# SCHEMATIC.net
KiCad netlist of a schematic drawn in EasyEDA
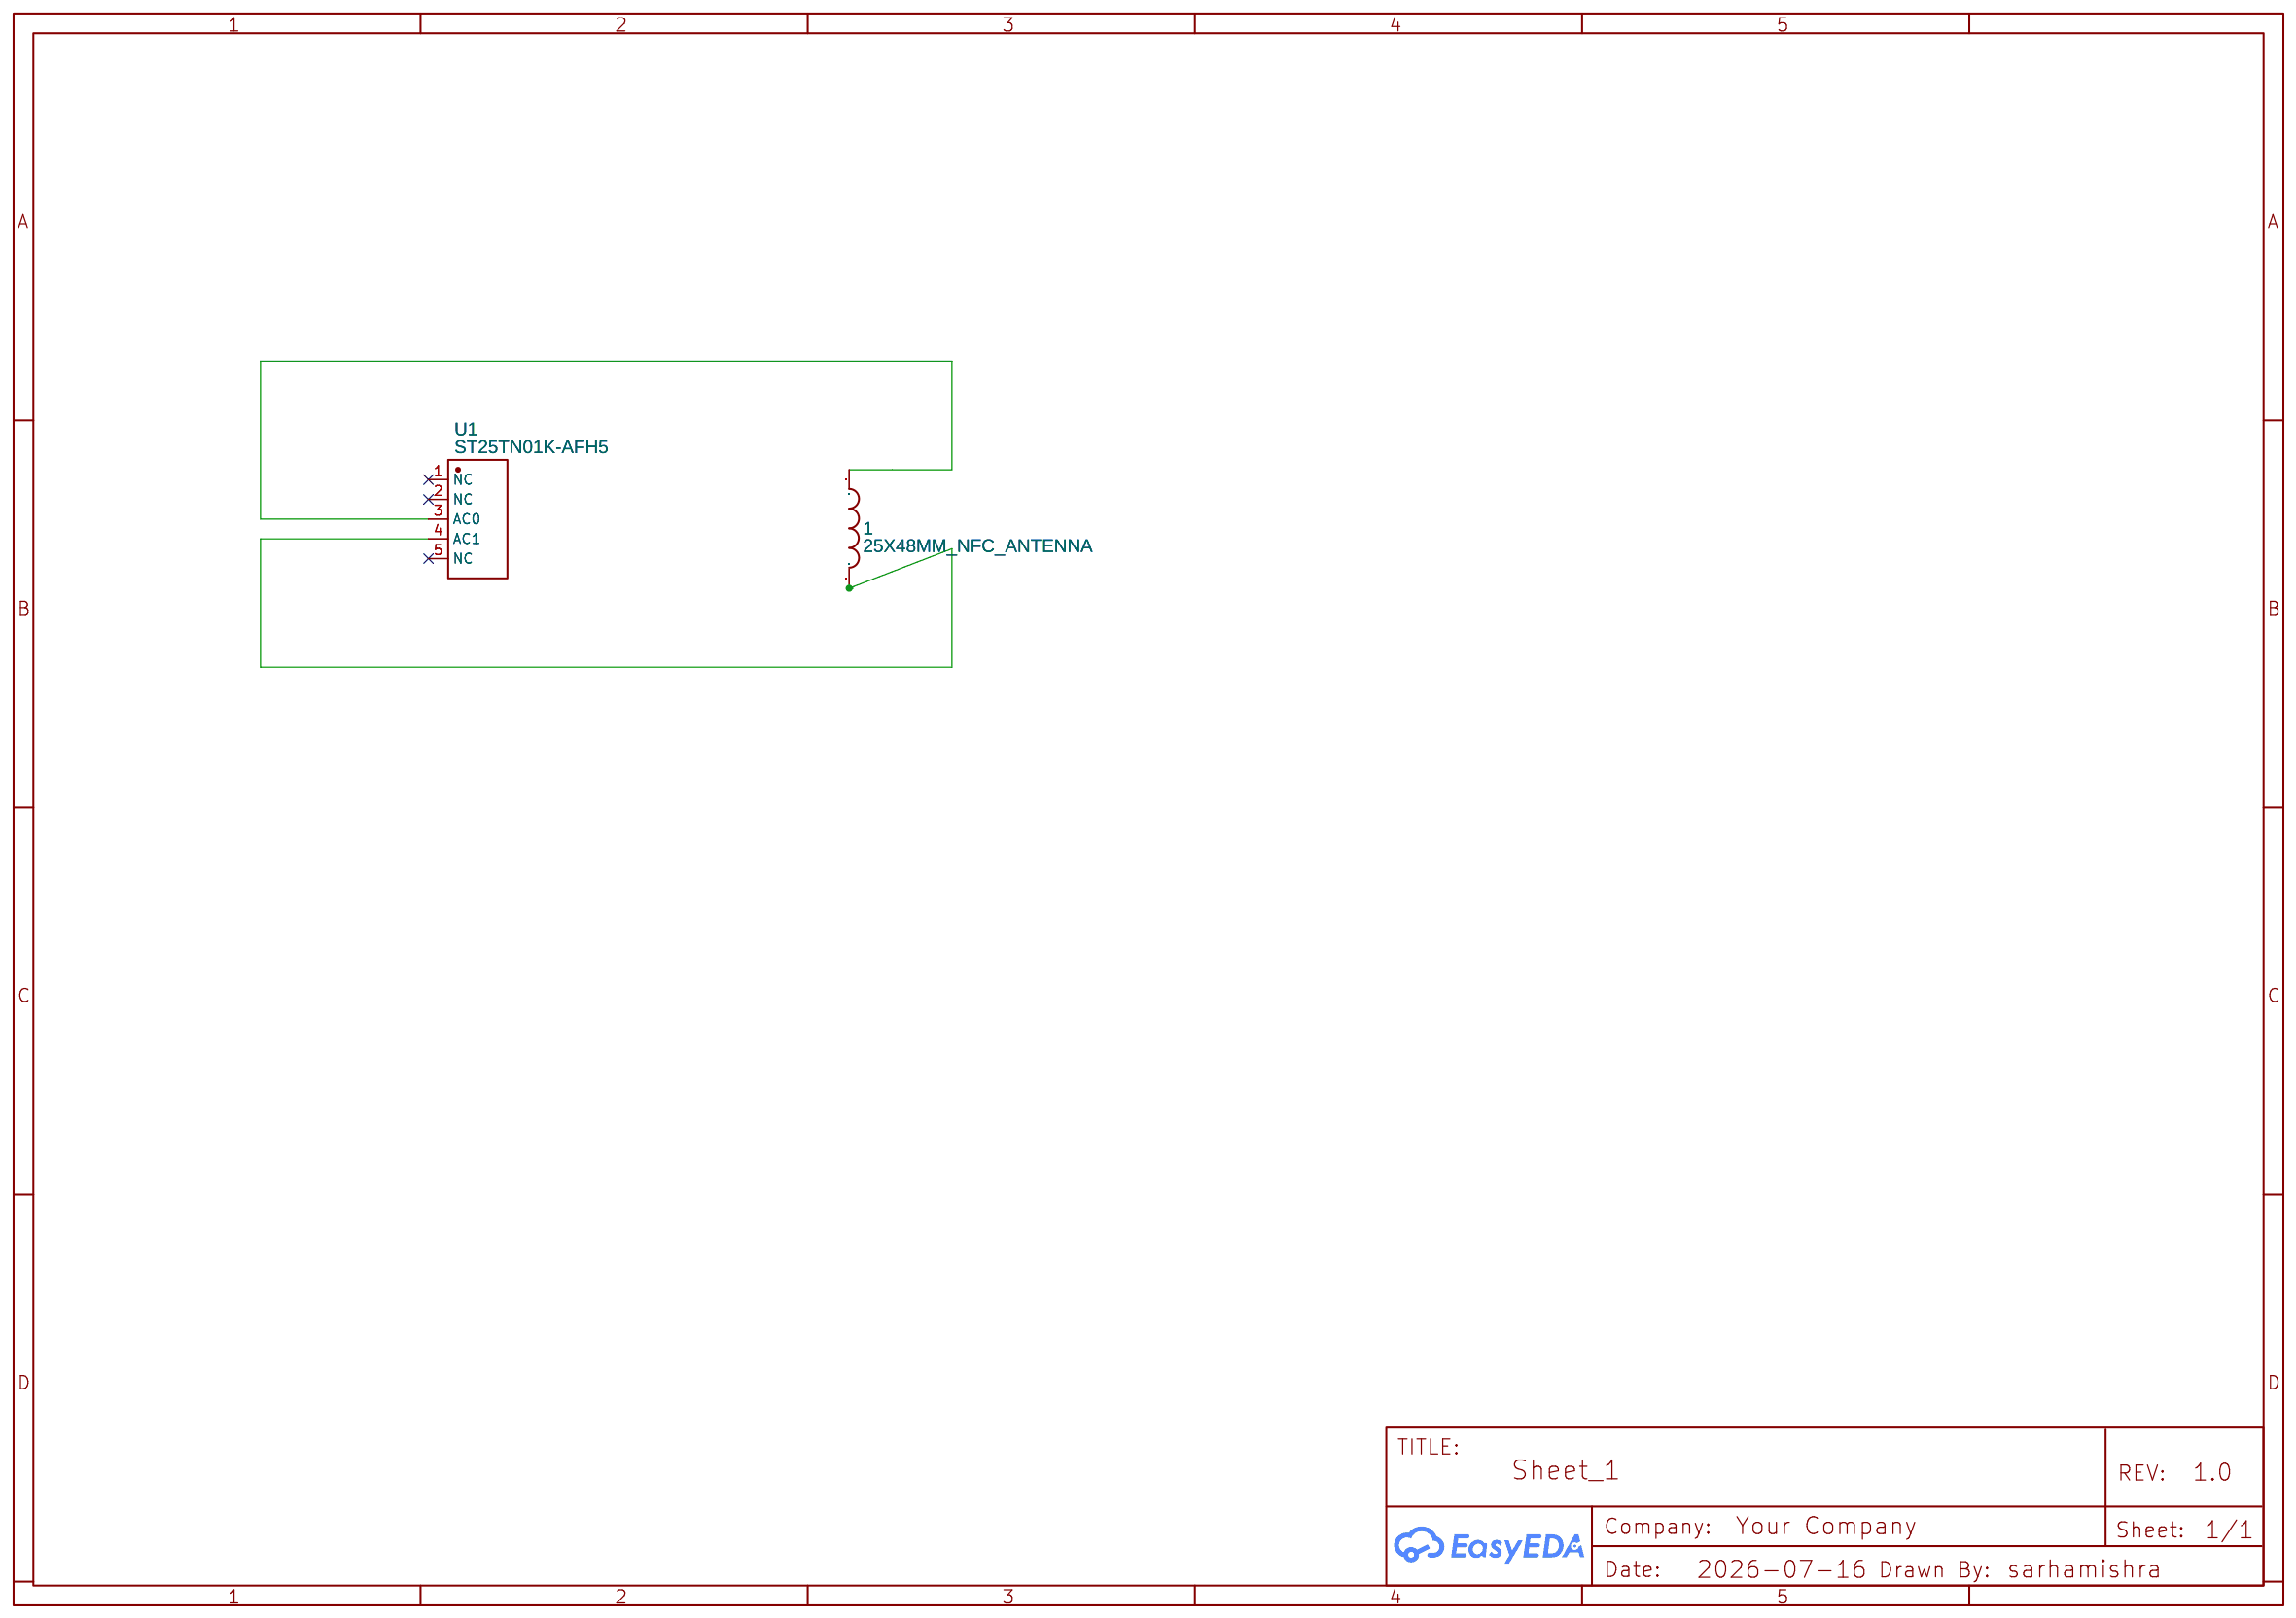
[diagram p0: schematic sheet]

(export (version "E")
  (design (tool "Eeschema 10.0.6"))
  (components
    (comp (ref "1") (value "25X48MM_NFC_ANTENNA") (libsource (lib "") (part "25X48MM_NFC_ANTENNA")))
    (comp (ref "U1")
      (value "ST25TN01K-AFH5")
      (fields (field (name "Manufacturer") "ST(意法半导体)"))
      (libsource (lib "") (part "ST25TN01K-AFH5"))
    )
  )
  (nets
    (net (code "1") (name "Net-(U1-AC0)") (class "Default")
      (node (ref "1") (pin "P$1") (pinfunction "P$1_P$1") (pintype "unspecified"))
      (node (ref "U1") (pin "3") (pinfunction "AC0_3") (pintype "unspecified"))
    )
    (net (code "2") (name "Net-(U1-AC1)") (class "Default")
      (node (ref "1") (pin "P$2") (pinfunction "P$2_P$2") (pintype "unspecified"))
      (node (ref "U1") (pin "4") (pinfunction "AC1_4") (pintype "unspecified"))
    )
    (net (code "3") (name "unconnected-(U1-NC-Pad1)") (class "Default")
      (node (ref "U1") (pin "1") (pinfunction "NC_1") (pintype "unspecified+no_connect"))
    )
    (net (code "4") (name "unconnected-(U1-NC-Pad2)") (class "Default")
      (node (ref "U1") (pin "2") (pinfunction "NC_2") (pintype "unspecified+no_connect"))
    )
    (net (code "5") (name "unconnected-(U1-NC-Pad5)") (class "Default")
      (node (ref "U1") (pin "5") (pinfunction "NC_5") (pintype "unspecified+no_connect"))
    )
  )
)
